# PowerChargingBoard_2025-02-05.net
KiCad netlist of a schematic drawn in Altium Designer
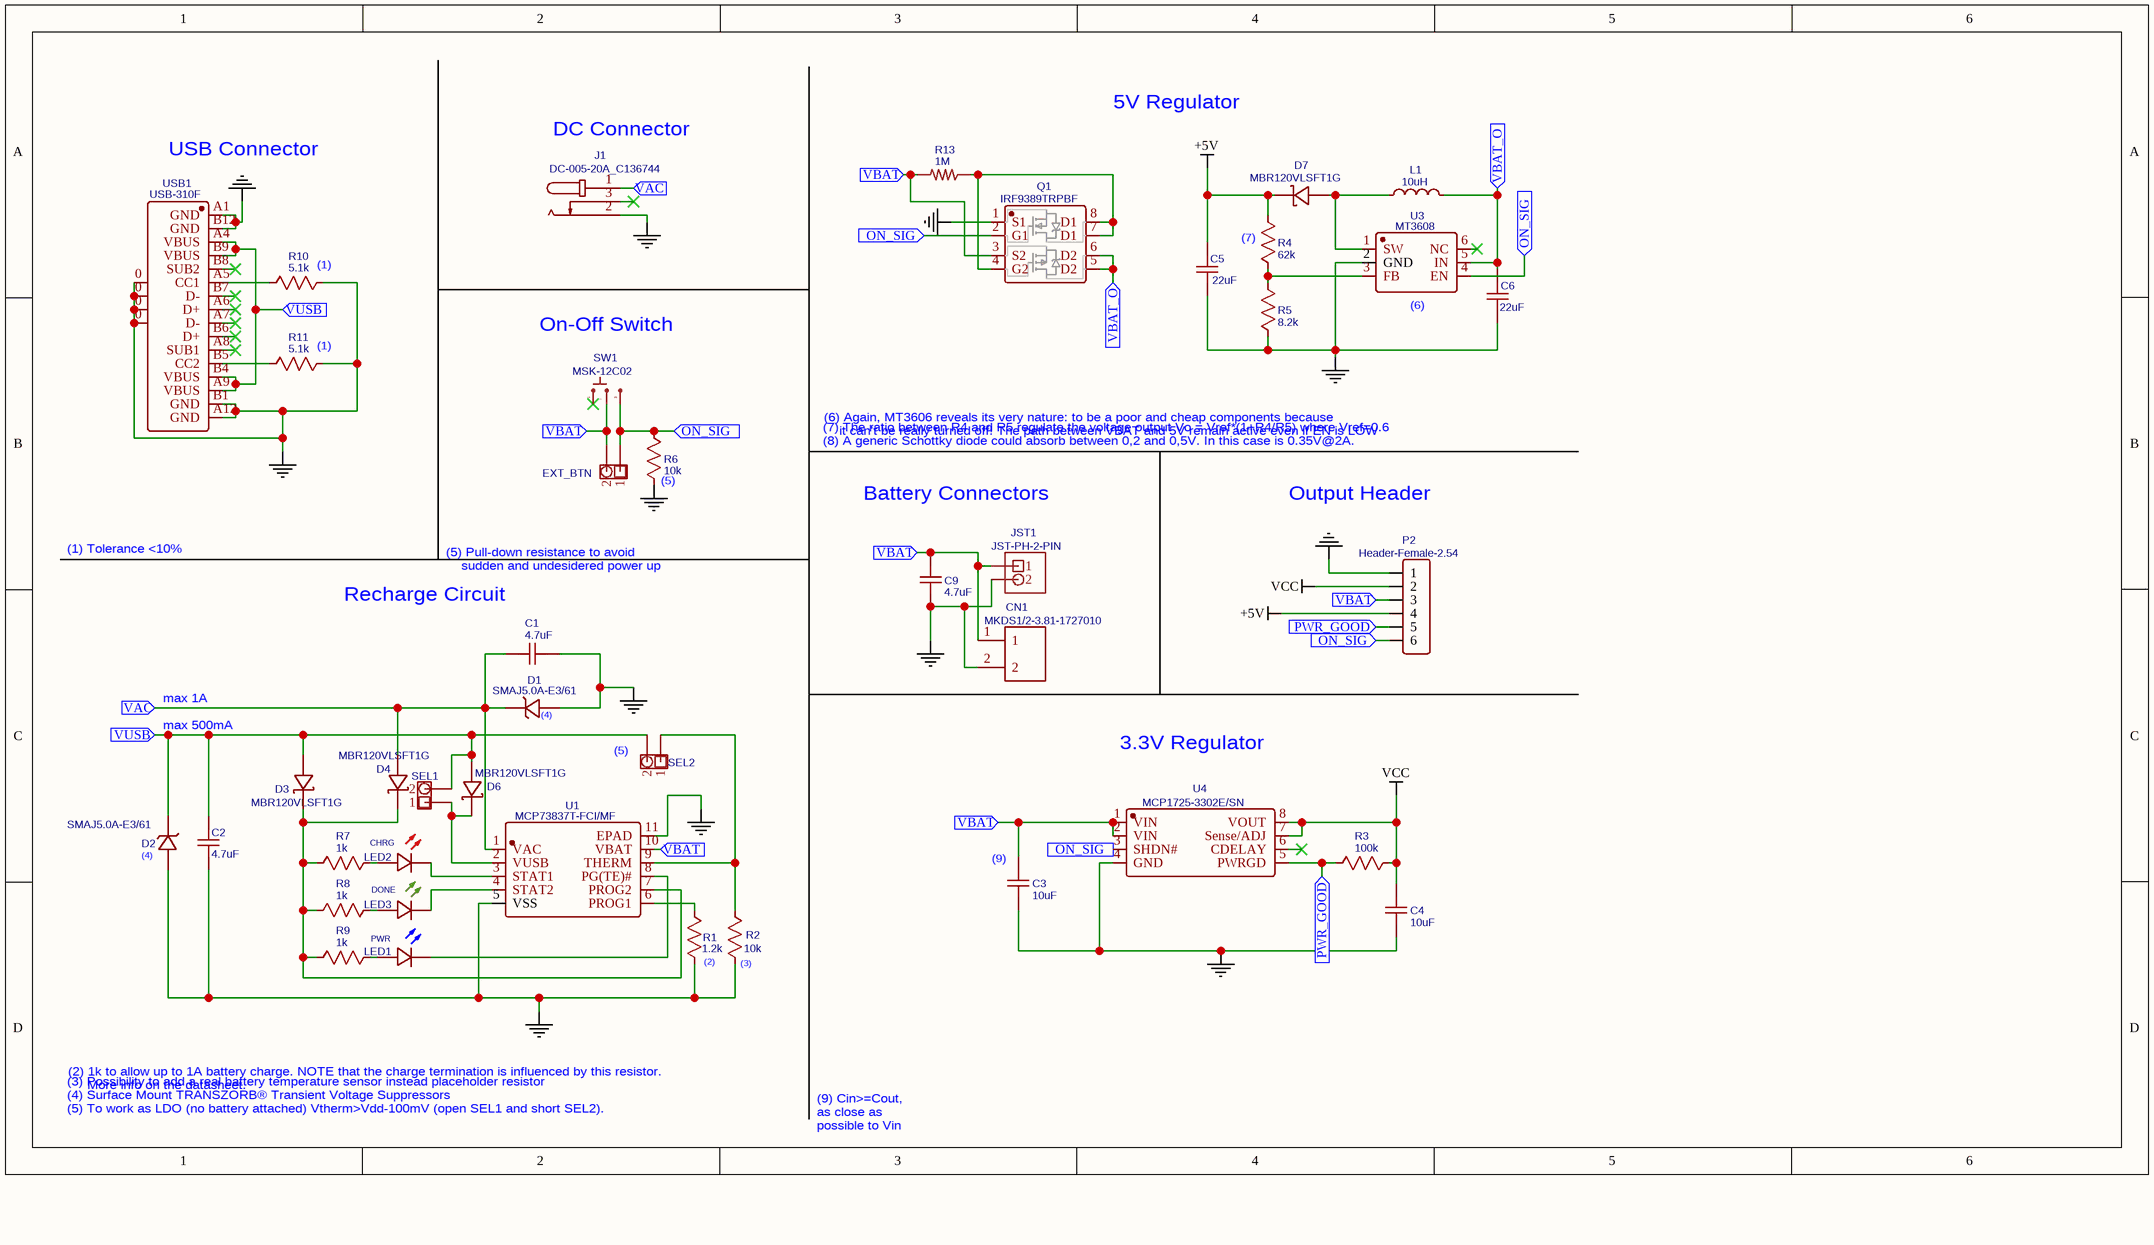
[diagram p0: PowerChargingBoard_2025-02-05.schdoc]

(export (version "E")
  (design (tool "Eeschema 10.0.6"))
  (components
    (comp (ref "C1")
      (value "4.7uF")
      (fields (field (name "MANUFACTURER PART") "?"))
      (libsource (lib "altium-import") (part "root_1_4.7uF_"))
    )
    (comp (ref "C2")
      (value "4.7uF")
      (fields (field (name "MANUFACTURER PART") "?"))
      (libsource (lib "altium-import") (part "root_0_4.7uF_"))
    )
    (comp (ref "C3")
      (value "10uF")
      (fields (field (name "MANUFACTURER PART") "?"))
      (libsource (lib "altium-import") (part "root_0_10uF_"))
    )
    (comp (ref "C4")
      (value "10uF")
      (fields (field (name "MANUFACTURER PART") "?"))
      (libsource (lib "altium-import") (part "root_0_10uF_"))
    )
    (comp (ref "C5")
      (value "22uF")
      (fields (field (name "MANUFACTURER PART") "?"))
      (libsource (lib "altium-import") (part "root_0_22uF_"))
    )
    (comp (ref "C6")
      (value "22uF")
      (fields (field (name "MANUFACTURER PART") "?"))
      (libsource (lib "altium-import") (part "root_0_22uF_"))
    )
    (comp (ref "C9")
      (value "4.7uF")
      (fields (field (name "MANUFACTURER PART") "?"))
      (libsource (lib "altium-import") (part "root_0_4.7uF_"))
    )
    (comp (ref "CN1")
      (value "MKDS1/2-3.81-1727010")
      (fields (field (name "MANUFACTURER") "Phoenix Contact"))
      (libsource (lib "altium-import") (part "root_0_MKDS1/2-3.81-1727010_"))
    )
    (comp (ref "D1")
      (value "SMAJ5.0A-E3/61")
      (fields (field (name "MANUFACTURER") "VISHAY"))
      (libsource (lib "altium-import") (part "root_0_SMAJ5.0A-E3/61_"))
    )
    (comp (ref "D2")
      (value "SMAJ5.0A-E3/61")
      (fields (field (name "MANUFACTURER") "VISHAY"))
      (libsource (lib "altium-import") (part "root_3_SMAJ5.0A-E3/61_"))
    )
    (comp (ref "D3")
      (value "MBR120VLSFT1G")
      (fields (field (name "MANUFACTURER") "ON Semicon") (field (name "CONTRIBUTOR") "LCSC"))
      (libsource (lib "altium-import") (part "root_1_MBR120VLSFT1G_"))
    )
    (comp (ref "D4")
      (value "MBR120VLSFT1G")
      (fields (field (name "MANUFACTURER") "ON Semicon") (field (name "CONTRIBUTOR") "LCSC"))
      (libsource (lib "altium-import") (part "root_1_MBR120VLSFT1G_"))
    )
    (comp (ref "D6")
      (value "MBR120VLSFT1G")
      (fields (field (name "MANUFACTURER") "ON Semicon") (field (name "CONTRIBUTOR") "LCSC"))
      (libsource (lib "altium-import") (part "root_1_MBR120VLSFT1G_"))
    )
    (comp (ref "D7")
      (value "MBR120VLSFT1G")
      (fields (field (name "MANUFACTURER") "ON Semicon") (field (name "CONTRIBUTOR") "LCSC"))
      (libsource (lib "altium-import") (part "root_0_MBR120VLSFT1G_"))
    )
    (comp (ref "EXT_BTN")
      (value "Just a couple of 2.54-spaced pins")
      (fields (field (name "MANUFACTURER PART") "?") (field (name "CONTRIBUTOR") "fabiano.riccardi"))
      (libsource (lib "altium-import") (part "root_3_Just a couple of 2.54-spaced pins_"))
    )
    (comp (ref "J1")
      (value "DC-005-20A_C136744")
      (fields
        (field (name "MANUFACTURER") "HRO")
        (field (name "MANUFACTURER PART") "DC-005-20A")
        (field (name "CONTRIBUTOR") "LCSC")
      )
      (libsource (lib "altium-import") (part "root_0_DC-005-20A_C136744_"))
    )
    (comp (ref "JST1")
      (value "JST-PH-2-PIN")
      (fields (field (name "CONTRIBUTOR") "fabiano.riccardi"))
      (libsource (lib "altium-import") (part "root_0_JST-PH-2-PIN_"))
    )
    (comp (ref "L1")
      (value "10uH")
      (fields
        (field (name "MANUFACTURER") "Murata Electronics")
        (field (name "MANUFACTURER PART") "LQH5BPN100M38L")
        (field (name "CONTRIBUTOR") "LCSC")
      )
      (libsource (lib "altium-import") (part "root_0_10uH_"))
    )
    (comp (ref "LED1")
      (value "PWR")
      (fields
        (field (name "MANUFACTURER") "Everlight Elec")
        (field (name "MANUFACTURER PART") "17-21/BHC-XL2M2TY/3T")
      )
      (libsource (lib "altium-import") (part "root_0_PWR_"))
    )
    (comp (ref "LED2")
      (value "CHRG")
      (fields
        (field (name "MANUFACTURER") "Everlight Elec")
        (field (name "MANUFACTURER PART") "17-21SURC/S530-A2/TR8")
      )
      (libsource (lib "altium-import") (part "root_0_CHRG_"))
    )
    (comp (ref "LED3")
      (value "DONE")
      (fields
        (field (name "MANUFACTURER") "Foshan NationStar Optoelectronics")
        (field (name "MANUFACTURER PART") "FC-DA1608UGK-520D10")
        (field (name "CONTRIBUTOR") "EasyEDA")
      )
      (libsource (lib "altium-import") (part "root_0_DONE_"))
    )
    (comp (ref "P2")
      (value "Header-Female-2.54")
      (fields (field (name "MANUFACTURER") "BOOMELE") (field (name "MANUFACTURER PART") "Female header 1*6p"))
      (libsource (lib "altium-import") (part "root_0_Header-Female-2.54_"))
    )
    (comp (ref "Q1")
      (value "IRF9389TRPBF")
      (fields (field (name "MANUFACTURER") "Infineon") (field (name "CONTRIBUTOR") "LCSC"))
      (libsource (lib "altium-import") (part "root_0_IRF9389TRPBF_"))
    )
    (comp (ref "R1")
      (value "1.2k")
      (fields (field (name "MANUFACTURER PART") "?"))
      (libsource (lib "altium-import") (part "root_1_1.2k_"))
    )
    (comp (ref "R2")
      (value "10k")
      (fields (field (name "MANUFACTURER PART") "?"))
      (libsource (lib "altium-import") (part "root_1_10k_"))
    )
    (comp (ref "R3")
      (value "100k")
      (fields (field (name "MANUFACTURER PART") "?"))
      (libsource (lib "altium-import") (part "root_0_100k_"))
    )
    (comp (ref "R4")
      (value "62k")
      (fields (field (name "MANUFACTURER PART") "?"))
      (libsource (lib "altium-import") (part "root_1_62k_"))
    )
    (comp (ref "R5")
      (value "8.2k")
      (fields (field (name "MANUFACTURER PART") "?"))
      (libsource (lib "altium-import") (part "root_1_8.2k_"))
    )
    (comp (ref "R6")
      (value "10k")
      (fields (field (name "MANUFACTURER PART") "?"))
      (libsource (lib "altium-import") (part "root_1_10k_"))
    )
    (comp (ref "R7")
      (value "1k")
      (fields (field (name "MANUFACTURER PART") "?"))
      (libsource (lib "altium-import") (part "root_0_1k_"))
    )
    (comp (ref "R8")
      (value "1k")
      (fields (field (name "MANUFACTURER PART") "?"))
      (libsource (lib "altium-import") (part "root_0_1k_"))
    )
    (comp (ref "R9")
      (value "1k")
      (fields (field (name "MANUFACTURER PART") "?"))
      (libsource (lib "altium-import") (part "root_0_1k_"))
    )
    (comp (ref "R10")
      (value "5.1k")
      (fields (field (name "MANUFACTURER PART") "?"))
      (libsource (lib "altium-import") (part "root_0_5.1k_"))
    )
    (comp (ref "R11")
      (value "5.1k")
      (fields (field (name "MANUFACTURER PART") "?"))
      (libsource (lib "altium-import") (part "root_0_5.1k_"))
    )
    (comp (ref "R13") (value "1M") (libsource (lib "altium-import") (part "root_2_1M_")))
    (comp (ref "SEL1")
      (value "Just a couple of 2.54-spaced pins")
      (fields (field (name "MANUFACTURER PART") "?") (field (name "CONTRIBUTOR") "fabiano.riccardi"))
      (libsource (lib "altium-import") (part "root_2_Just a couple of 2.54-spaced pins_"))
    )
    (comp (ref "SEL2")
      (value "Just a couple of 2.54-spaced pins")
      (fields (field (name "MANUFACTURER PART") "?") (field (name "CONTRIBUTOR") "fabiano.riccardi"))
      (libsource (lib "altium-import") (part "root_3_Just a couple of 2.54-spaced pins_"))
    )
    (comp (ref "SW1")
      (value "MSK-12C02")
      (fields (field (name "MANUFACTURER PART") "?") (field (name "MANUFACTURER") "SHOU HAN"))
      (libsource (lib "altium-import") (part "root_1_MSK-12C02_"))
    )
    (comp (ref "U1")
      (value "MCP73837T-FCI/MF")
      (fields (field (name "MANUFACTURER") "Microchip Tech") (field (name "CONTRIBUTOR") "LCSC"))
      (libsource (lib "altium-import") (part "root_0_MCP73837T-FCI/MF_"))
    )
    (comp (ref "U3")
      (value "MT3608")
      (fields (field (name "MANUFACTURER") "AEROSEMI"))
      (libsource (lib "altium-import") (part "root_0_MT3608_"))
    )
    (comp (ref "U4")
      (value "MCP1725-3302E/SN")
      (fields (field (name "MANUFACTURER") "Microchip Tech") (field (name "CONTRIBUTOR") "fabiano.riccardi"))
      (libsource (lib "altium-import") (part "root_0_MCP1725-3302E/SN_"))
    )
    (comp (ref "USB1")
      (value "USB-310F")
      (fields (field (name "MANUFACTURER") "HOOYA") (field (name "CONTRIBUTOR") "LCSC"))
      (libsource (lib "altium-import") (part "root_0_USB-310F_"))
    )
  )
  (nets
    (net (code "1") (name "+5V") (class "Default")
      (node (ref "C5") (pin "2") (pinfunction "2_2") (pintype "passive"))
      (node (ref "D7") (pin "1") (pinfunction "K_1") (pintype "passive"))
      (node (ref "P2") (pin "4") (pinfunction "4_4") (pintype "passive"))
      (node (ref "R4") (pin "2") (pinfunction "2_2") (pintype "passive"))
    )
    (net (code "2") (name "/ON_SIG") (class "Default")
      (node (ref "EXT_BTN") (pin "1") (pinfunction "1_1") (pintype "passive"))
      (node (ref "P2") (pin "6") (pinfunction "6_6") (pintype "passive"))
      (node (ref "Q1") (pin "2") (pinfunction "G1_2") (pintype "passive"))
      (node (ref "R6") (pin "2") (pinfunction "2_2") (pintype "passive"))
      (node (ref "SW1") (pin "3") (pinfunction "3_3") (pintype "passive"))
      (node (ref "U3") (pin "4") (pinfunction "EN_4") (pintype "passive"))
      (node (ref "U4") (pin "3") (pinfunction "SHDN#_3") (pintype "passive"))
    )
    (net (code "3") (name "/PWR_GOOD") (class "Default")
      (node (ref "P2") (pin "5") (pinfunction "5_5") (pintype "passive"))
      (node (ref "R3") (pin "1") (pinfunction "1_1") (pintype "passive"))
      (node (ref "U4") (pin "5") (pinfunction "PWRGD_5") (pintype "passive"))
    )
    (net (code "4") (name "/VAC") (class "Default")
      (node (ref "C1") (pin "2") (pinfunction "2_2") (pintype "passive"))
      (node (ref "D1") (pin "1") (pinfunction "C_1") (pintype "passive"))
      (node (ref "D4") (pin "2") (pinfunction "A_2") (pintype "passive"))
      (node (ref "J1") (pin "1") (pinfunction "1_1") (pintype "passive"))
      (node (ref "U1") (pin "1") (pinfunction "VAC_1") (pintype "passive"))
    )
    (net (code "5") (name "/VBAT") (class "Default")
      (node (ref "C3") (pin "2") (pinfunction "2_2") (pintype "passive"))
      (node (ref "C9") (pin "2") (pinfunction "2_2") (pintype "passive"))
      (node (ref "CN1") (pin "1") (pinfunction "1_1") (pintype "passive"))
      (node (ref "EXT_BTN") (pin "2") (pinfunction "2_2") (pintype "passive"))
      (node (ref "JST1") (pin "1") (pinfunction "1_1") (pintype "passive"))
      (node (ref "P2") (pin "3") (pinfunction "3_3") (pintype "passive"))
      (node (ref "Q1") (pin "3") (pinfunction "S2_3") (pintype "passive"))
      (node (ref "R13") (pin "2") (pinfunction "2_2") (pintype "passive"))
      (node (ref "SW1") (pin "2") (pinfunction "2_2") (pintype "passive"))
      (node (ref "U1") (pin "10") (pinfunction "VBAT_10") (pintype "passive"))
      (node (ref "U4") (pin "1") (pinfunction "VIN_1") (pintype "passive"))
      (node (ref "U4") (pin "2") (pinfunction "VIN_2") (pintype "passive"))
    )
    (net (code "6") (name "/VBAT_O") (class "Default")
      (node (ref "C6") (pin "2") (pinfunction "2_2") (pintype "passive"))
      (node (ref "L1") (pin "2") (pinfunction "2_2") (pintype "passive"))
      (node (ref "Q1") (pin "5") (pinfunction "D2_5") (pintype "passive"))
      (node (ref "Q1") (pin "6") (pinfunction "D2_6") (pintype "passive"))
      (node (ref "U3") (pin "5") (pinfunction "IN_5") (pintype "passive"))
    )
    (net (code "7") (name "/VUSB") (class "Default")
      (node (ref "C2") (pin "2") (pinfunction "2_2") (pintype "passive"))
      (node (ref "D2") (pin "1") (pinfunction "C_1") (pintype "passive"))
      (node (ref "D3") (pin "2") (pinfunction "A_2") (pintype "passive"))
      (node (ref "D6") (pin "2") (pinfunction "A_2") (pintype "passive"))
      (node (ref "SEL1") (pin "2") (pinfunction "2_2") (pintype "passive"))
      (node (ref "SEL2") (pin "2") (pinfunction "2_2") (pintype "passive"))
      (node (ref "USB1") (pin "A4") (pinfunction "VBUS_A4") (pintype "passive"))
      (node (ref "USB1") (pin "A9") (pinfunction "VBUS_A9") (pintype "passive"))
      (node (ref "USB1") (pin "B4") (pinfunction "VBUS_B4") (pintype "passive"))
      (node (ref "USB1") (pin "B9") (pinfunction "VBUS_B9") (pintype "passive"))
    )
    (net (code "8") (name "GND") (class "Default")
      (node (ref "C1") (pin "1") (pinfunction "1_1") (pintype "passive"))
      (node (ref "C2") (pin "1") (pinfunction "1_1") (pintype "passive"))
      (node (ref "C3") (pin "1") (pinfunction "1_1") (pintype "passive"))
      (node (ref "C4") (pin "1") (pinfunction "1_1") (pintype "passive"))
      (node (ref "C5") (pin "1") (pinfunction "1_1") (pintype "passive"))
      (node (ref "C6") (pin "1") (pinfunction "1_1") (pintype "passive"))
      (node (ref "C9") (pin "1") (pinfunction "1_1") (pintype "passive"))
      (node (ref "CN1") (pin "2") (pinfunction "2_2") (pintype "passive"))
      (node (ref "D1") (pin "2") (pinfunction "A_2") (pintype "passive"))
      (node (ref "D2") (pin "2") (pinfunction "A_2") (pintype "passive"))
      (node (ref "J1") (pin "2") (pinfunction "2_2") (pintype "passive"))
      (node (ref "JST1") (pin "2") (pinfunction "2_2") (pintype "passive"))
      (node (ref "P2") (pin "1") (pinfunction "1_1") (pintype "passive"))
      (node (ref "Q1") (pin "1") (pinfunction "S1_1") (pintype "passive"))
      (node (ref "R1") (pin "1") (pinfunction "1_1") (pintype "passive"))
      (node (ref "R10") (pin "2") (pinfunction "2_2") (pintype "passive"))
      (node (ref "R11") (pin "2") (pinfunction "2_2") (pintype "passive"))
      (node (ref "R2") (pin "1") (pinfunction "1_1") (pintype "passive"))
      (node (ref "R5") (pin "1") (pinfunction "1_1") (pintype "passive"))
      (node (ref "R6") (pin "1") (pinfunction "1_1") (pintype "passive"))
      (node (ref "U1") (pin "11") (pinfunction "EPAD_11") (pintype "passive"))
      (node (ref "U1") (pin "5") (pinfunction "VSS_5") (pintype "passive"))
      (node (ref "U3") (pin "2") (pinfunction "GND_2") (pintype "passive"))
      (node (ref "U4") (pin "4") (pinfunction "GND_4") (pintype "passive"))
      (node (ref "USB1") (pin "0") (pinfunction "0_0") (pintype "passive"))
      (node (ref "USB1") (pin "A1") (pinfunction "GND_A1") (pintype "passive"))
      (node (ref "USB1") (pin "A12") (pinfunction "GND_A12") (pintype "passive"))
      (node (ref "USB1") (pin "B1") (pinfunction "GND_B1") (pintype "passive"))
      (node (ref "USB1") (pin "B12") (pinfunction "GND_B12") (pintype "passive"))
    )
    (net (code "9") (name "Net-(D3-K)") (class "Default")
      (node (ref "D3") (pin "1") (pinfunction "K_1") (pintype "passive"))
      (node (ref "D4") (pin "1") (pinfunction "K_1") (pintype "passive"))
      (node (ref "R7") (pin "1") (pinfunction "1_1") (pintype "passive"))
      (node (ref "R8") (pin "1") (pinfunction "1_1") (pintype "passive"))
      (node (ref "R9") (pin "1") (pinfunction "1_1") (pintype "passive"))
      (node (ref "U1") (pin "7") (pinfunction "PROG2_7") (pintype "passive"))
    )
    (net (code "10") (name "Net-(D6-K)") (class "Default")
      (node (ref "D6") (pin "1") (pinfunction "K_1") (pintype "passive"))
      (node (ref "SEL1") (pin "1") (pinfunction "1_1") (pintype "passive"))
      (node (ref "U1") (pin "2") (pinfunction "VUSB_2") (pintype "passive"))
    )
    (net (code "11") (name "Net-(D7-A)") (class "Default")
      (node (ref "D7") (pin "2") (pinfunction "A_2") (pintype "passive"))
      (node (ref "L1") (pin "1") (pinfunction "1_1") (pintype "passive"))
      (node (ref "U3") (pin "1") (pinfunction "SW_1") (pintype "passive"))
    )
    (net (code "12") (name "Net-(LED1-+)") (class "Default")
      (node (ref "LED1") (pin "1") (pinfunction "+_1") (pintype "passive"))
      (node (ref "R9") (pin "2") (pinfunction "2_2") (pintype "passive"))
    )
    (net (code "13") (name "Net-(LED1--)") (class "Default")
      (node (ref "LED1") (pin "2") (pinfunction "-_2") (pintype "passive"))
      (node (ref "U1") (pin "8") (pinfunction "PG(TE)#_8") (pintype "passive"))
    )
    (net (code "14") (name "Net-(LED2-+)") (class "Default")
      (node (ref "LED2") (pin "1") (pinfunction "+_1") (pintype "passive"))
      (node (ref "R7") (pin "2") (pinfunction "2_2") (pintype "passive"))
    )
    (net (code "15") (name "Net-(LED2--)") (class "Default")
      (node (ref "LED2") (pin "2") (pinfunction "-_2") (pintype "passive"))
      (node (ref "U1") (pin "3") (pinfunction "STAT1_3") (pintype "passive"))
    )
    (net (code "16") (name "Net-(LED3-+)") (class "Default")
      (node (ref "LED3") (pin "1") (pinfunction "+_1") (pintype "passive"))
      (node (ref "R8") (pin "2") (pinfunction "2_2") (pintype "passive"))
    )
    (net (code "17") (name "Net-(LED3--)") (class "Default")
      (node (ref "LED3") (pin "2") (pinfunction "-_2") (pintype "passive"))
      (node (ref "U1") (pin "4") (pinfunction "STAT2_4") (pintype "passive"))
    )
    (net (code "18") (name "Net-(Q1-G2)") (class "Default")
      (node (ref "Q1") (pin "4") (pinfunction "G2_4") (pintype "passive"))
      (node (ref "Q1") (pin "7") (pinfunction "D1_7") (pintype "passive"))
      (node (ref "Q1") (pin "8") (pinfunction "D1_8") (pintype "passive"))
      (node (ref "R13") (pin "1") (pinfunction "1_1") (pintype "passive"))
    )
    (net (code "19") (name "Net-(U1-PROG1)") (class "Default")
      (node (ref "R1") (pin "2") (pinfunction "2_2") (pintype "passive"))
      (node (ref "U1") (pin "6") (pinfunction "PROG1_6") (pintype "passive"))
    )
    (net (code "20") (name "Net-(U1-THERM)") (class "Default")
      (node (ref "R2") (pin "2") (pinfunction "2_2") (pintype "passive"))
      (node (ref "SEL2") (pin "1") (pinfunction "1_1") (pintype "passive"))
      (node (ref "U1") (pin "9") (pinfunction "THERM_9") (pintype "passive"))
    )
    (net (code "21") (name "Net-(U3-FB)") (class "Default")
      (node (ref "R4") (pin "1") (pinfunction "1_1") (pintype "passive"))
      (node (ref "R5") (pin "2") (pinfunction "2_2") (pintype "passive"))
      (node (ref "U3") (pin "3") (pinfunction "FB_3") (pintype "passive"))
    )
    (net (code "22") (name "Net-(USB1-CC1)") (class "Default")
      (node (ref "R10") (pin "1") (pinfunction "1_1") (pintype "passive"))
      (node (ref "USB1") (pin "A5") (pinfunction "CC1_A5") (pintype "passive"))
    )
    (net (code "23") (name "Net-(USB1-CC2)") (class "Default")
      (node (ref "R11") (pin "1") (pinfunction "1_1") (pintype "passive"))
      (node (ref "USB1") (pin "B5") (pinfunction "CC2_B5") (pintype "passive"))
    )
    (net (code "24") (name "VCC") (class "Default")
      (node (ref "C4") (pin "2") (pinfunction "2_2") (pintype "passive"))
      (node (ref "P2") (pin "2") (pinfunction "2_2") (pintype "passive"))
      (node (ref "R3") (pin "2") (pinfunction "2_2") (pintype "passive"))
      (node (ref "U4") (pin "7") (pinfunction "Sense/ADJ_7") (pintype "passive"))
      (node (ref "U4") (pin "8") (pinfunction "VOUT_8") (pintype "passive"))
    )
    (net (code "25") (name "unconnected-(J1-Pad3)") (class "Default")
      (node (ref "J1") (pin "3") (pinfunction "3_3") (pintype "passive+no_connect"))
    )
    (net (code "26") (name "unconnected-(SW1-Pad1)") (class "Default")
      (node (ref "SW1") (pin "1") (pinfunction "1_1") (pintype "passive+no_connect"))
    )
    (net (code "27") (name "unconnected-(U3-NC-Pad6)") (class "Default")
      (node (ref "U3") (pin "6") (pinfunction "NC_6") (pintype "passive+no_connect"))
    )
    (net (code "28") (name "unconnected-(U4-CDELAY-Pad6)") (class "Default")
      (node (ref "U4") (pin "6") (pinfunction "CDELAY_6") (pintype "passive+no_connect"))
    )
    (net (code "29") (name "unconnected-(USB1-D+-PadA6)") (class "Default")
      (node (ref "USB1") (pin "A6") (pinfunction "D+_A6") (pintype "passive+no_connect"))
    )
    (net (code "30") (name "unconnected-(USB1-D+-PadB6)") (class "Default")
      (node (ref "USB1") (pin "B6") (pinfunction "D+_B6") (pintype "passive+no_connect"))
    )
    (net (code "31") (name "unconnected-(USB1-D--PadA7)") (class "Default")
      (node (ref "USB1") (pin "A7") (pinfunction "D-_A7") (pintype "passive+no_connect"))
    )
    (net (code "32") (name "unconnected-(USB1-D--PadB7)") (class "Default")
      (node (ref "USB1") (pin "B7") (pinfunction "D-_B7") (pintype "passive+no_connect"))
    )
    (net (code "33") (name "unconnected-(USB1-SUB1-PadA8)") (class "Default")
      (node (ref "USB1") (pin "A8") (pinfunction "SUB1_A8") (pintype "passive+no_connect"))
    )
    (net (code "34") (name "unconnected-(USB1-SUB2-PadB8)") (class "Default")
      (node (ref "USB1") (pin "B8") (pinfunction "SUB2_B8") (pintype "passive+no_connect"))
    )
  )
)
